# USB_PD_Source.net
KiCad netlist of a schematic drawn in Altium Designer
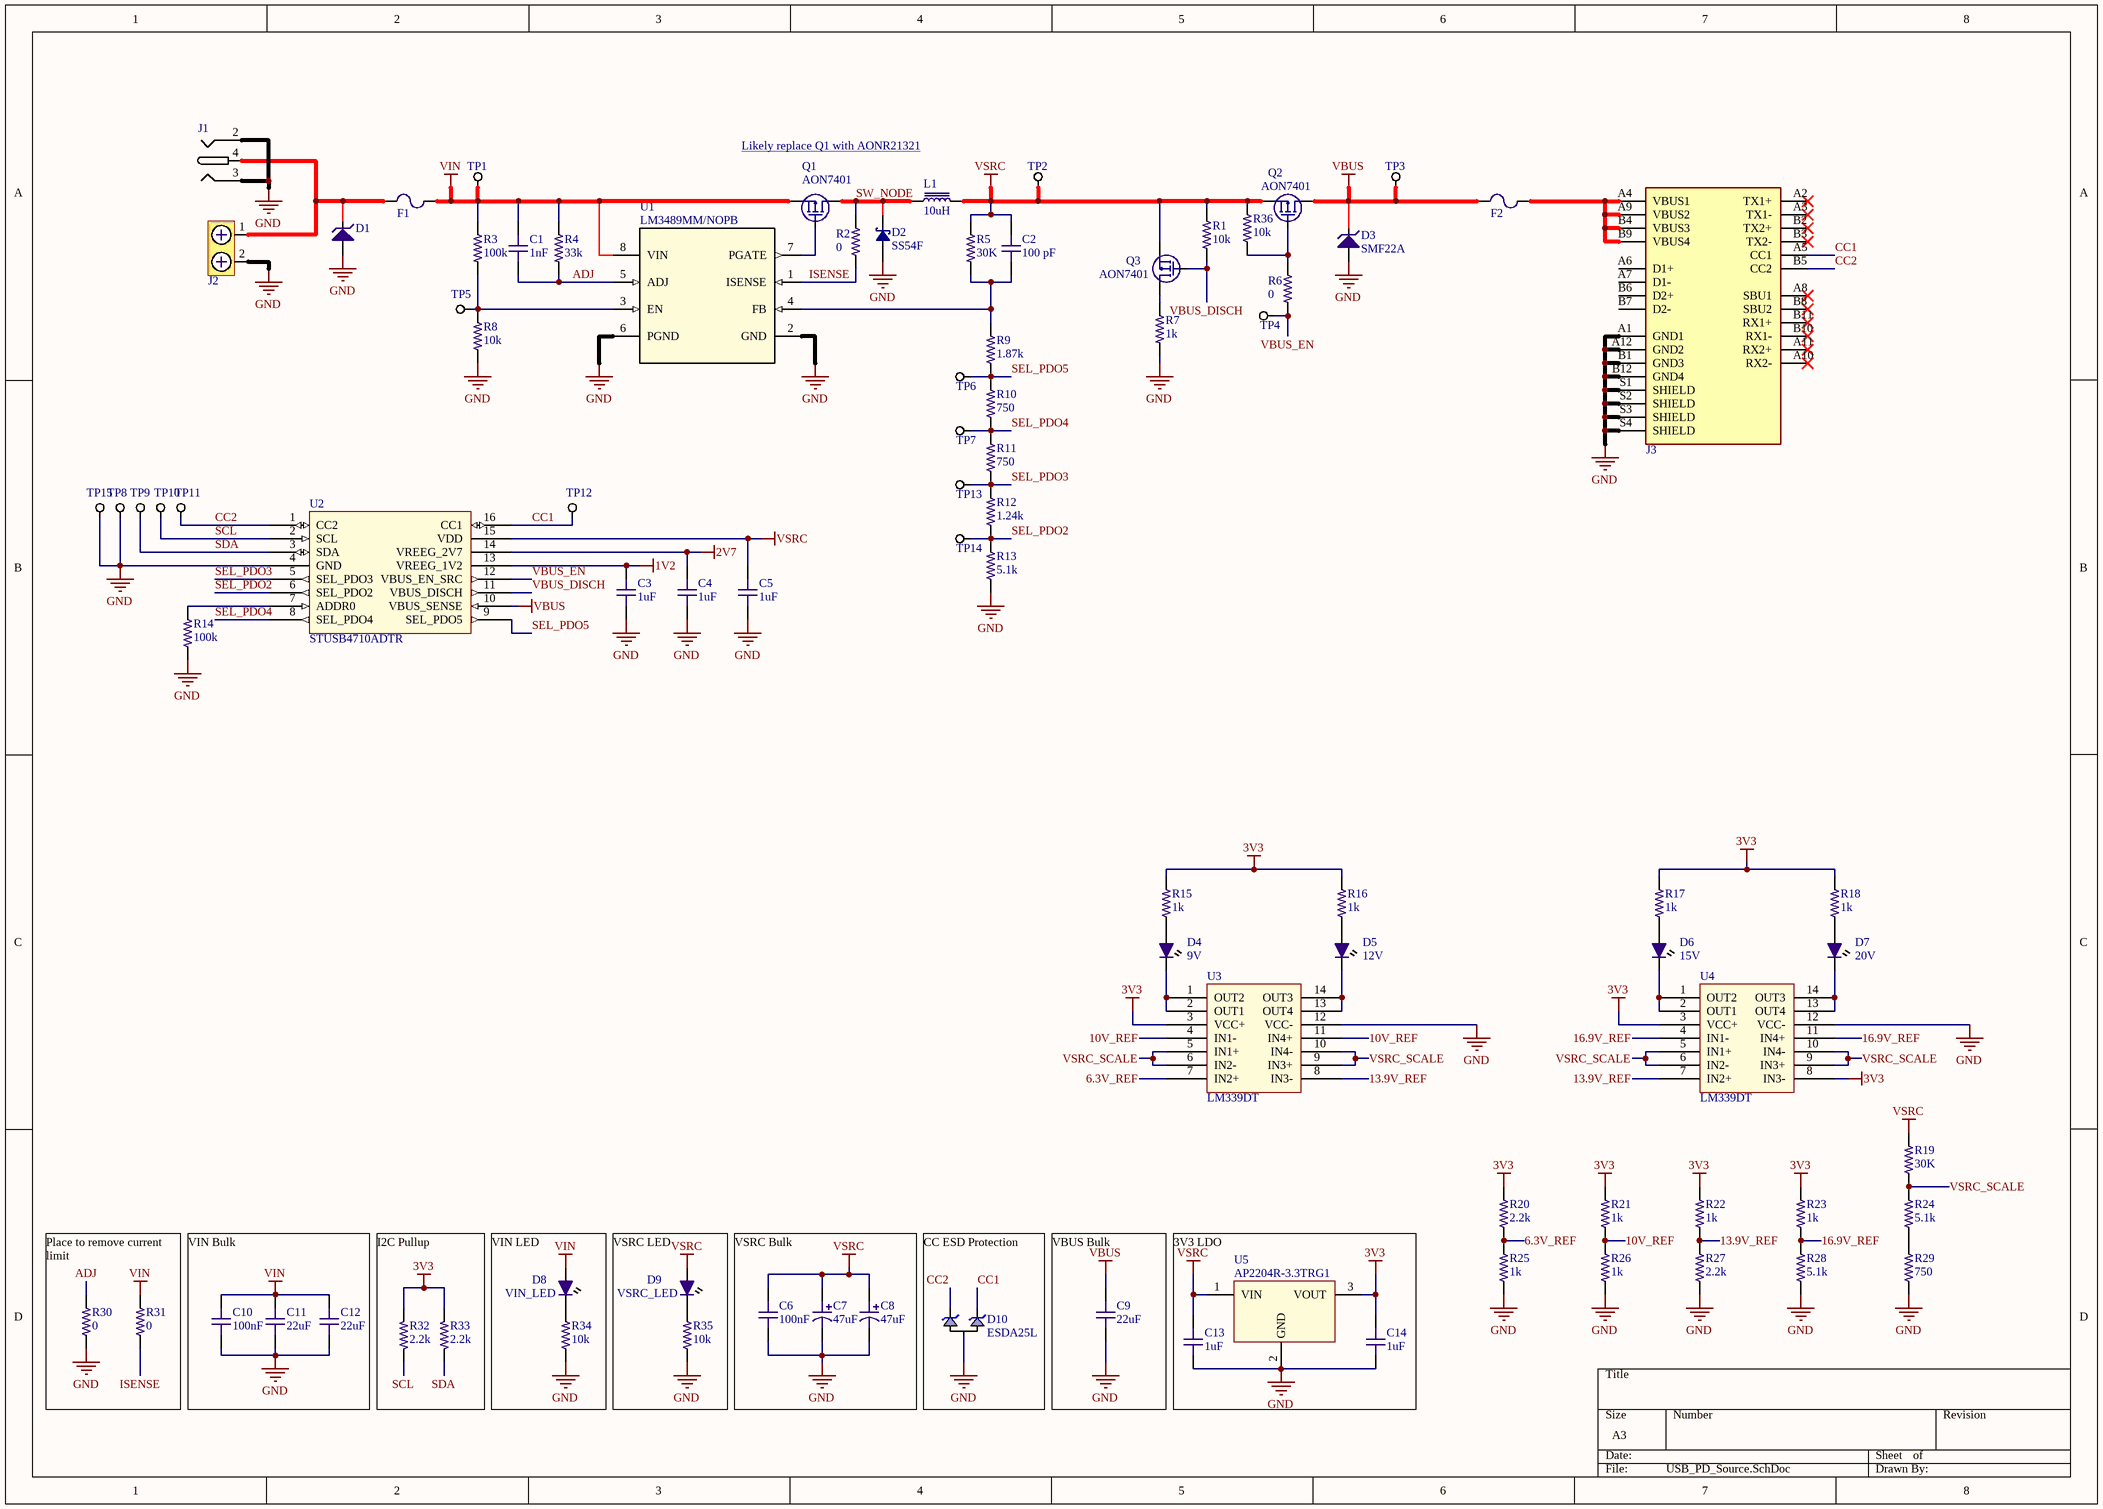
[diagram p0: USB_PD_Source.SchDoc]

(export (version "E")
  (design (tool "Eeschema 10.0.6"))
  (components
    (comp (ref "C1")
      (value "1nF")
      (footprint "C0603-IPC")
      (description "CAP CER 1000PF 100V X7R 0603")
      (fields (field (name "Comment") "C0603 1nF 100V X7R"))
      (libsource (lib "Capacitors") (part "C0603 1nF 100V X7R"))
    )
    (comp (ref "C2")
      (value "100 pF")
      (footprint "C0603-HIGH-DENSITY")
      (description "100pF ±10% 50V Ceramic Capacitor X7R 0603 (1608 Metric)")
      (fields (field (name "Comment") "C0603 100pF 50V X7R"))
      (libsource (lib "Capacitors") (part "C0603 100pF 50V X7R"))
    )
    (comp (ref "C3")
      (value "1uF")
      (footprint "C0603-IPC")
      (description "CAP CER 1UF 25V X7R 0603")
      (fields (field (name "Comment") "C0603 1uF 25V X7R"))
      (libsource (lib "Capacitors") (part "C0603 1uF 25V X7R"))
    )
    (comp (ref "C4")
      (value "1uF")
      (footprint "C0603-IPC")
      (description "CAP CER 1UF 25V X7R 0603")
      (fields (field (name "Comment") "C0603 1uF 25V X7R"))
      (libsource (lib "Capacitors") (part "C0603 1uF 25V X7R"))
    )
    (comp (ref "C5")
      (value "1uF")
      (footprint "C0603-IPC")
      (description "CAP CER 1UF 25V X7R 0603")
      (fields (field (name "Comment") "C0603 1uF 25V X7R"))
      (libsource (lib "Capacitors") (part "C0603 1uF 25V X7R"))
    )
    (comp (ref "C6")
      (value "100nF")
      (footprint "C0603-IPC")
      (description "CAP CER 0.1UF 50V X7R 0603")
      (fields (field (name "Comment") "C0603 100nF 50V X7R"))
      (libsource (lib "Capacitors") (part "C0603 100nF 50V X7R"))
    )
    (comp (ref "C7")
      (value "47uF")
      (footprint "C-SMD-Polarized-6.3x7.7mm")
      (description "47uF ±20% 50V SMD,6.3x7.7mm Aluminum Electrolytic Capacitors - SMD")
      (fields (field (name "Comment") "UUR1H470MCL6GS"))
      (libsource (lib "Capacitors") (part "C-SMD 47uF 50V Electrolytic"))
    )
    (comp (ref "C8")
      (value "47uF")
      (footprint "C-SMD-Polarized-6.3x7.7mm")
      (description "47uF ±20% 50V SMD,6.3x7.7mm Aluminum Electrolytic Capacitors - SMD")
      (fields (field (name "Comment") "UUR1H470MCL6GS"))
      (libsource (lib "Capacitors") (part "C-SMD 47uF 50V Electrolytic"))
    )
    (comp (ref "C9")
      (value "22uF")
      (footprint "C0603-IPC")
      (description "Chip Capacitor, 0603, 22uF, 25V, X5R")
      (fields (field (name "Comment") "C0603 22uF 25V X5R"))
      (libsource (lib "Capacitors") (part "C0603 22uF 10V X5R"))
    )
    (comp (ref "C10")
      (value "100nF")
      (footprint "C0603-IPC")
      (description "CAP CER 0.1UF 50V X7R 0603")
      (fields (field (name "Comment") "C0603 100nF 50V X7R"))
      (libsource (lib "Capacitors") (part "C0603 100nF 50V X7R"))
    )
    (comp (ref "C11")
      (value "22uF")
      (footprint "C0603-IPC")
      (description "Chip Capacitor, 0603, 22uF, 25V, X5R")
      (fields (field (name "Comment") "C0603 22uF 25V X5R"))
      (libsource (lib "Capacitors") (part "C0603 22uF 10V X5R"))
    )
    (comp (ref "C12")
      (value "22uF")
      (footprint "C0603-IPC")
      (description "Chip Capacitor, 0603, 22uF, 25V, X5R")
      (fields (field (name "Comment") "C0603 22uF 25V X5R"))
      (libsource (lib "Capacitors") (part "C0603 22uF 10V X5R"))
    )
    (comp (ref "C13")
      (value "1uF")
      (footprint "C0603-IPC")
      (description "CAP CER 1UF 25V X7R 0603")
      (fields (field (name "Comment") "C0603 1uF 25V X7R"))
      (libsource (lib "Capacitors") (part "C0603 1uF 25V X7R"))
    )
    (comp (ref "C14")
      (value "1uF")
      (footprint "C0603-IPC")
      (description "CAP CER 1UF 25V X7R 0603")
      (fields (field (name "Comment") "C0603 1uF 25V X7R"))
      (libsource (lib "Capacitors") (part "C0603 1uF 25V X7R"))
    )
    (comp (ref "D1")
      (value "GLZJ33C_R1_10001")
      (footprint "Mini-MELF Zener")
      (description "33V 500mW MINI-MELF Zener Diodes")
      (fields (field (name "MANUFACTURER") "PANJIT International"))
      (libsource (lib "Diodes") (part "GLZJ33C_R1_10001"))
    )
    (comp (ref "D2")
      (value "SS54F")
      (footprint "SMAF - SS54F")
      (description "40V 5A 550mV @ 5A SMAF Schottky Barrier Diodes (SBD) RoHS")
      (libsource (lib "Diodes") (part "SS54F"))
    )
    (comp (ref "D3")
      (value "SMF22A")
      (footprint "SOD-123F")
      (description "Unidirectional 22V 24.4V 35.5V 5.6A SOD-123F TVS RoHS")
      (fields (field (name "MANUFACTURER") "Littlefuse Inc."))
      (libsource (lib "Diodes") (part "SMF22A"))
    )
    (comp (ref "D4")
      (value "9V")
      (footprint "LED0603-IPC")
      (description "LED GREEN CLEAR 0603 SMD")
      (libsource (lib "Diodes") (part "LED 0603 Green"))
    )
    (comp (ref "D5")
      (value "12V")
      (footprint "LED0603-IPC")
      (description "LED GREEN CLEAR 0603 SMD")
      (libsource (lib "Diodes") (part "LED 0603 Green"))
    )
    (comp (ref "D6")
      (value "15V")
      (footprint "LED0603-IPC")
      (description "LED GREEN CLEAR 0603 SMD")
      (libsource (lib "Diodes") (part "LED 0603 Green"))
    )
    (comp (ref "D7")
      (value "20V")
      (footprint "LED0603-IPC")
      (description "LED GREEN CLEAR 0603 SMD")
      (libsource (lib "Diodes") (part "LED 0603 Green"))
    )
    (comp (ref "D8")
      (value "VIN_LED")
      (footprint "LED0603-IPC")
      (description "LED GREEN CLEAR 0603 SMD")
      (libsource (lib "Diodes") (part "LED 0603 Green"))
    )
    (comp (ref "D9")
      (value "VSRC_LED")
      (footprint "LED0603-IPC")
      (description "LED GREEN CLEAR 0603 SMD")
      (libsource (lib "Diodes") (part "LED 0603 Green"))
    )
    (comp (ref "D10")
      (value "ESDA25L")
      (footprint "SOT23-3L")
      (description "Dual Transil Array For ESD Protection in SOT23-3 Vbr = 25V")
      (fields (field (name "MANUFACTURER") "STMicroelectronics"))
      (libsource (lib "Diodes") (part "ESDA25L"))
    )
    (comp (ref "F1")
      (value "JFC1206-2150FS")
      (footprint "F1206-12A")
      (description "Chip Fuse Fast Blow 15A 2.9mΩ 66mV 150A 23.89 1206 Surface Mount Fuses")
      (libsource (lib "Virtual Parts") (part "F1206 15A"))
    )
    (comp (ref "F2")
      (value "JFC1206-2150FS")
      (footprint "F1206-12A")
      (description "Chip Fuse Fast Blow 15A 2.9mΩ 66mV 150A 23.89 1206 Surface Mount Fuses")
      (libsource (lib "Virtual Parts") (part "F1206 15A"))
    )
    (comp (ref "J1")
      (value "DC-042C-2.5")
      (footprint "DC-042C-2.5 THT BARREL JACK")
      (description "DC Power Receptacle Jack 8A 2.5mm DIP AC/DC Power Plugs & Receptacles")
      (libsource (lib "Connectors") (part "DC Barrel Jack 2.5 x 5.5mm THT"))
    )
    (comp (ref "J2")
      (value "Phoenix Contact 1935161")
      (footprint "Phoenix_1935161")
      (description "Terminal Block, 2 Position, 5mm pitch, 18A, 300V, 12-26 AWG")
      (fields
        (field (name "MANUFACTURER") "Phoenix Contact")
        (field (name "MANUFACTURER PART NUMBER") "1935161")
      )
      (libsource (lib "Connectors") (part "Term Block 2pos"))
    )
    (comp (ref "J3")
      (value "USB C")
      (footprint "Molex USB-C")
      (fields
        (field (name "MF") "Molex")
        (field (name "DIGI-KEY_PART_NUMBER") "WM12856CT-ND")
        (field (name "MP") "1054500101")
      )
      (libsource (lib "Connectors") (part "USB C"))
    )
    (comp (ref "L1")
      (value "TMPA1206SP-100MN-D")
      (footprint "TMPA1206SP-100MN-D")
      (description "10uH ±20% 10.5A 15.5mΩ SMD,13.5x12.6x5.7mm Power Inductors RoHS")
      (fields (field (name "INDUCTANCE") "10uH"))
      (libsource (lib "Inductors") (part "TMPA1206SP-100MN-D"))
    )
    (comp (ref "Q1")
      (value "AON7401")
      (footprint "DFN3x3A_8L_EP1_P")
      (description "P-Channel 30V 12A (Ta), 35A (Tc) 3.1W (Ta), 29W (Tc) Surface Mount 8-DFN (3x3)")
      (libsource (lib "Transistors") (part "AON7401"))
    )
    (comp (ref "Q2")
      (value "AON7401")
      (footprint "DFN3x3A_8L_EP1_P")
      (description "P-Channel 30V 12A (Ta), 35A (Tc) 3.1W (Ta), 29W (Tc) Surface Mount 8-DFN (3x3)")
      (libsource (lib "Transistors") (part "AON7401"))
    )
    (comp (ref "Q3")
      (value "AON7401")
      (footprint "DFN3x3A_8L_EP1_P")
      (description "P-Channel 30V 12A (Ta), 35A (Tc) 3.1W (Ta), 29W (Tc) Surface Mount 8-DFN (3x3)")
      (libsource (lib "Transistors") (part "AON7401"))
    )
    (comp (ref "R1")
      (value "10k")
      (footprint "R0603-IPC-10K")
      (description "RES SMD 10K OHM 1% 1/10W 0603")
      (fields (field (name "Comment") "R0603 10K 1%"))
      (libsource (lib "Resistors") (part "R0603 10K 1%"))
    )
    (comp (ref "R2")
      (value "0")
      (footprint "R0603-IPC")
      (description "RES SMD 0 OHM JUMPER 1/10W 0603")
      (fields (field (name "Comment") "R0603 0"))
      (libsource (lib "Resistors") (part "R0603 0"))
    )
    (comp (ref "R3")
      (value "100k")
      (footprint "R0603-IPC")
      (description "RES SMD 100K OHM 1% 1/10W 0603")
      (fields (field (name "Comment") "R0603 100K 1%"))
      (libsource (lib "Resistors") (part "R0603 100K 1%"))
    )
    (comp (ref "R4")
      (value "33k")
      (footprint "R0603-IPC")
      (description "RES 33K OHM 1% 1/10W 0603")
      (fields (field (name "Comment") "R0603 33k 1%"))
      (libsource (lib "Resistors") (part "R0603 33k 1%"))
    )
    (comp (ref "R5")
      (value "30K")
      (footprint "R0603-IPC")
      (description "RES SMD 30K OHM 1% 1/10W 0603")
      (fields (field (name "Comment") "R0603 30k 1%"))
      (libsource (lib "Resistors") (part "R0603 30k 1%"))
    )
    (comp (ref "R6")
      (value "0")
      (footprint "R0603-IPC")
      (description "RES SMD 0 OHM JUMPER 1/10W 0603")
      (fields (field (name "Comment") "R0603 0"))
      (libsource (lib "Resistors") (part "R0603 0"))
    )
    (comp (ref "R7")
      (value "1k")
      (footprint "R0603-IPC-1K")
      (description "RES SMD 1K OHM 1% 1/10W 0603")
      (fields (field (name "TOLERANCE") "±1%") (field (name "Comment") "R0603 1K 1%"))
      (libsource (lib "Resistors") (part "R0603 1K 1%"))
    )
    (comp (ref "R8")
      (value "10k")
      (footprint "R0603-IPC-10K")
      (description "RES SMD 10K OHM 1% 1/10W 0603")
      (fields (field (name "Comment") "R0603 10K 1%"))
      (libsource (lib "Resistors") (part "R0603 10K 1%"))
    )
    (comp (ref "R9")
      (value "1.87k")
      (footprint "R0603-IPC-1.87k")
      (description "Chip Resistor, 0603, 1.87k ohms, 1%, 1/10 W")
      (fields (field (name "Comment") "RES 1.87K SMD"))
      (libsource (lib "Resistors") (part "R0603 1.87k 1%"))
    )
    (comp (ref "R10")
      (value "750")
      (footprint "R0603-IPC-750R")
      (description "Chip Resistor, 0603, 750 ohms, 0.1W")
      (fields (field (name "Comment") "R0603 750 1%"))
      (libsource (lib "Resistors") (part "R0603 750 1%"))
    )
    (comp (ref "R11")
      (value "750")
      (footprint "R0603-IPC-750R")
      (description "Chip Resistor, 0603, 750 ohms, 0.1W")
      (fields (field (name "Comment") "R0603 750 1%"))
      (libsource (lib "Resistors") (part "R0603 750 1%"))
    )
    (comp (ref "R12")
      (value "1.24k")
      (footprint "R0603-IPC")
      (description "Chip Resistor, 0603, 1.24k ohms, 0.5%, 1/10 W")
      (fields (field (name "Comment") "ERA3AED1241V"))
      (libsource (lib "Resistors") (part "R0603 1.24k 0.5%"))
    )
    (comp (ref "R13")
      (value "5.1k")
      (footprint "R0603-IPC-5.1K")
      (description "RES SMD 5.1K OHM 1% 1/10W 0603")
      (fields (field (name "Comment") "R0603 5.1K 1%"))
      (libsource (lib "Resistors") (part "R0603 5.1K 1%"))
    )
    (comp (ref "R14")
      (value "100k")
      (footprint "R0603-IPC")
      (description "RES SMD 100K OHM 1% 1/10W 0603")
      (fields (field (name "Comment") "R0603 100K 1%"))
      (libsource (lib "Resistors") (part "R0603 100K 1%"))
    )
    (comp (ref "R15")
      (value "1k")
      (footprint "R0603-IPC-1K")
      (description "RES SMD 1K OHM 1% 1/10W 0603")
      (fields (field (name "TOLERANCE") "±1%") (field (name "Comment") "R0603 1K 1%"))
      (libsource (lib "Resistors") (part "R0603 1K 1%"))
    )
    (comp (ref "R16")
      (value "1k")
      (footprint "R0603-IPC-1K")
      (description "RES SMD 1K OHM 1% 1/10W 0603")
      (fields (field (name "TOLERANCE") "±1%") (field (name "Comment") "R0603 1K 1%"))
      (libsource (lib "Resistors") (part "R0603 1K 1%"))
    )
    (comp (ref "R17")
      (value "1k")
      (footprint "R0603-IPC-1K")
      (description "RES SMD 1K OHM 1% 1/10W 0603")
      (fields (field (name "TOLERANCE") "±1%") (field (name "Comment") "R0603 1K 1%"))
      (libsource (lib "Resistors") (part "R0603 1K 1%"))
    )
    (comp (ref "R18")
      (value "1k")
      (footprint "R0603-IPC-1K")
      (description "RES SMD 1K OHM 1% 1/10W 0603")
      (fields (field (name "TOLERANCE") "±1%") (field (name "Comment") "R0603 1K 1%"))
      (libsource (lib "Resistors") (part "R0603 1K 1%"))
    )
    (comp (ref "R19")
      (value "30K")
      (footprint "R0603-IPC")
      (description "RES SMD 30K OHM 1% 1/10W 0603")
      (fields (field (name "Comment") "R0603 30k 1%"))
      (libsource (lib "Resistors") (part "R0603 30k 1%"))
    )
    (comp (ref "R20")
      (value "2.2k")
      (footprint "R0603-IPC")
      (description "RES SMD 2.2K OHM 1% 1/10W 0603")
      (fields (field (name "Comment") "R0603 2.2K 1%"))
      (libsource (lib "Resistors") (part "R0603 2.2K 1%"))
    )
    (comp (ref "R21")
      (value "1k")
      (footprint "R0603-IPC-1K")
      (description "RES SMD 1K OHM 1% 1/10W 0603")
      (fields (field (name "TOLERANCE") "±1%") (field (name "Comment") "R0603 1K 1%"))
      (libsource (lib "Resistors") (part "R0603 1K 1%"))
    )
    (comp (ref "R22")
      (value "1k")
      (footprint "R0603-IPC-1K")
      (description "RES SMD 1K OHM 1% 1/10W 0603")
      (fields (field (name "TOLERANCE") "±1%") (field (name "Comment") "R0603 1K 1%"))
      (libsource (lib "Resistors") (part "R0603 1K 1%"))
    )
    (comp (ref "R23")
      (value "1k")
      (footprint "R0603-IPC-1K")
      (description "RES SMD 1K OHM 1% 1/10W 0603")
      (fields (field (name "TOLERANCE") "±1%") (field (name "Comment") "R0603 1K 1%"))
      (libsource (lib "Resistors") (part "R0603 1K 1%"))
    )
    (comp (ref "R24")
      (value "5.1k")
      (footprint "R0603-IPC-5.1K")
      (description "RES SMD 5.1K OHM 1% 1/10W 0603")
      (fields (field (name "Comment") "R0603 5.1K 1%"))
      (libsource (lib "Resistors") (part "R0603 5.1K 1%"))
    )
    (comp (ref "R25")
      (value "1k")
      (footprint "R0603-IPC-1K")
      (description "RES SMD 1K OHM 1% 1/10W 0603")
      (fields (field (name "TOLERANCE") "±1%") (field (name "Comment") "R0603 1K 1%"))
      (libsource (lib "Resistors") (part "R0603 1K 1%"))
    )
    (comp (ref "R26")
      (value "1k")
      (footprint "R0603-IPC-1K")
      (description "RES SMD 1K OHM 1% 1/10W 0603")
      (fields (field (name "TOLERANCE") "±1%") (field (name "Comment") "R0603 1K 1%"))
      (libsource (lib "Resistors") (part "R0603 1K 1%"))
    )
    (comp (ref "R27")
      (value "2.2k")
      (footprint "R0603-IPC")
      (description "RES SMD 2.2K OHM 1% 1/10W 0603")
      (fields (field (name "Comment") "R0603 2.2K 1%"))
      (libsource (lib "Resistors") (part "R0603 2.2K 1%"))
    )
    (comp (ref "R28")
      (value "5.1k")
      (footprint "R0603-IPC-5.1K")
      (description "RES SMD 5.1K OHM 1% 1/10W 0603")
      (fields (field (name "Comment") "R0603 5.1K 1%"))
      (libsource (lib "Resistors") (part "R0603 5.1K 1%"))
    )
    (comp (ref "R29")
      (value "750")
      (footprint "R0603-IPC-750R")
      (description "Chip Resistor, 0603, 750 ohms, 0.1W")
      (fields (field (name "Comment") "R0603 750 1%"))
      (libsource (lib "Resistors") (part "R0603 750 1%"))
    )
    (comp (ref "R30")
      (value "0")
      (footprint "R0603-IPC")
      (description "RES SMD 0 OHM JUMPER 1/10W 0603")
      (fields (field (name "Comment") "R0603 0"))
      (libsource (lib "Resistors") (part "R0603 0"))
    )
    (comp (ref "R31")
      (value "0")
      (footprint "R0603-IPC")
      (description "RES SMD 0 OHM JUMPER 1/10W 0603")
      (fields (field (name "Comment") "R0603 0"))
      (libsource (lib "Resistors") (part "R0603 0"))
    )
    (comp (ref "R32")
      (value "2.2k")
      (footprint "R0603-IPC")
      (description "RES SMD 2.2K OHM 1% 1/10W 0603")
      (fields (field (name "Comment") "R0603 2.2K 1%"))
      (libsource (lib "Resistors") (part "R0603 2.2K 1%"))
    )
    (comp (ref "R33")
      (value "2.2k")
      (footprint "R0603-IPC")
      (description "RES SMD 2.2K OHM 1% 1/10W 0603")
      (fields (field (name "Comment") "R0603 2.2K 1%"))
      (libsource (lib "Resistors") (part "R0603 2.2K 1%"))
    )
    (comp (ref "R34")
      (value "10k")
      (footprint "R0603-HIGH-DENSITY")
      (description "RES SMD 10K OHM 1% 1/10W 0603")
      (fields (field (name "Comment") "R0603 10K 1%"))
      (libsource (lib "Resistors") (part "R0603 10K 1%"))
    )
    (comp (ref "R35")
      (value "10k")
      (footprint "R0603-IPC-10K")
      (description "RES SMD 10K OHM 1% 1/10W 0603")
      (fields (field (name "Comment") "R0603 10K 1%"))
      (libsource (lib "Resistors") (part "R0603 10K 1%"))
    )
    (comp (ref "R36")
      (value "10k")
      (footprint "R0603-IPC-10K")
      (description "RES SMD 10K OHM 1% 1/10W 0603")
      (fields (field (name "Comment") "R0603 10K 1%"))
      (libsource (lib "Resistors") (part "R0603 10K 1%"))
    )
    (comp (ref "TP1")
      (value "VIN")
      (footprint "Testpoint_TH")
      (description "Through-hole testpoint hook")
      (libsource (lib "Virtual Parts") (part "Testpoint_TH"))
    )
    (comp (ref "TP2")
      (value "VSRC")
      (footprint "Testpoint_TH")
      (description "Through-hole testpoint hook")
      (libsource (lib "Virtual Parts") (part "Testpoint_TH"))
    )
    (comp (ref "TP3")
      (value "VBUS")
      (footprint "Testpoint_TH")
      (description "Through-hole testpoint hook")
      (libsource (lib "Virtual Parts") (part "Testpoint_TH"))
    )
    (comp (ref "TP4")
      (value "VBUS_EN")
      (footprint "Testpoint_TH")
      (description "Through-hole testpoint hook")
      (libsource (lib "Virtual Parts") (part "Testpoint_TH"))
    )
    (comp (ref "TP5")
      (value "BUCK_EN")
      (footprint "Testpoint_TH")
      (description "Through-hole testpoint hook")
      (libsource (lib "Virtual Parts") (part "Testpoint_TH"))
    )
    (comp (ref "TP6")
      (value "PDO2_N")
      (footprint "Testpoint_TH")
      (description "Through-hole testpoint hook")
      (libsource (lib "Virtual Parts") (part "Testpoint_TH"))
    )
    (comp (ref "TP7")
      (value "PDO3_N")
      (footprint "Testpoint_TH")
      (description "Through-hole testpoint hook")
      (libsource (lib "Virtual Parts") (part "Testpoint_TH"))
    )
    (comp (ref "TP8")
      (value "GNDD")
      (footprint "Testpoint_TH")
      (description "Through-hole testpoint hook")
      (libsource (lib "Virtual Parts") (part "Testpoint_TH"))
    )
    (comp (ref "TP9")
      (value "SDA")
      (footprint "Testpoint_TH")
      (description "Through-hole testpoint hook")
      (libsource (lib "Virtual Parts") (part "Testpoint_TH"))
    )
    (comp (ref "TP10")
      (value "SCL")
      (footprint "Testpoint_TH")
      (description "Through-hole testpoint hook")
      (libsource (lib "Virtual Parts") (part "Testpoint_TH"))
    )
    (comp (ref "TP11")
      (value "CC2")
      (footprint "Testpoint_TH")
      (description "Through-hole testpoint hook")
      (libsource (lib "Virtual Parts") (part "Testpoint_TH"))
    )
    (comp (ref "TP12")
      (value "CC1")
      (footprint "Testpoint_TH")
      (description "Through-hole testpoint hook")
      (libsource (lib "Virtual Parts") (part "Testpoint_TH"))
    )
    (comp (ref "TP13")
      (value "PDO4_N")
      (footprint "Testpoint_TH")
      (description "Through-hole testpoint hook")
      (libsource (lib "Virtual Parts") (part "Testpoint_TH"))
    )
    (comp (ref "TP14")
      (value "PDO5_N")
      (footprint "Testpoint_TH")
      (description "Through-hole testpoint hook")
      (libsource (lib "Virtual Parts") (part "Testpoint_TH"))
    )
    (comp (ref "TP15")
      (value "Testpoint_TH")
      (footprint "Testpoint_TH")
      (description "Through-hole testpoint hook")
      (libsource (lib "Virtual Parts") (part "Testpoint_TH"))
    )
    (comp (ref "U1")
      (value "LM3489MM/NOPB")
      (footprint "DGK (S-PDSO-G8) - LM3489")
      (description "Buck Regulator Positive Output Step-Down DC-DC Controller IC 8-VSSOP")
      (libsource (lib "Integrated Circuits") (part "LM3489MM"))
    )
    (comp (ref "U2")
      (value "STUSB4710ADTR")
      (footprint "SO-16")
      (description "Standalone USB PD controller  with Source in 16-SO package")
      (fields
        (field (name "PART NUMBER") "Standalone USB PD controller  with SINK auto-run mode in QFN24 4x4mm")
        (field (name "MANUFACTURER") "STMicroelectronics")
      )
      (libsource (lib "Integrated Circuits") (part "STUSB4710ADTR"))
    )
    (comp (ref "U3")
      (value "LM339DT")
      (footprint "SO-14 (LM339DT)")
      (description "Quad Comparator General Purpose CMOS, DTL, ECL, MOS, Open-Collector, TTL 14-SO, 2-32V")
      (libsource (lib "Integrated Circuits") (part "LM339DT"))
    )
    (comp (ref "U4")
      (value "LM339DT")
      (footprint "SO-14 (LM339DT)")
      (description "Quad Comparator General Purpose CMOS, DTL, ECL, MOS, Open-Collector, TTL 14-SO, 2-32V")
      (libsource (lib "Integrated Circuits") (part "LM339DT"))
    )
    (comp (ref "U5")
      (value "AP2204R-3.3TRG1")
      (footprint "SOT-89")
      (description "Fixed 24V 3.3V 150mA SOT-89(SOT-89-3) Low Dropout Regulators(LDO)")
      (libsource (lib "Integrated Circuits") (part "AP2204R-3.3TRG1"))
    )
  )
  (nets
    (net (code "1") (name "/6.3V_REF") (class "Default")
      (node (ref "R20") (pin "1") (pintype "passive"))
      (node (ref "R25") (pin "1") (pintype "passive"))
      (node (ref "U3") (pin "7") (pinfunction "IN2+_7") (pintype "passive"))
    )
    (net (code "2") (name "/10V_REF") (class "Default")
      (node (ref "R21") (pin "2") (pintype "passive"))
      (node (ref "R26") (pin "1") (pintype "passive"))
      (node (ref "U3") (pin "11") (pinfunction "IN4+_11") (pintype "passive"))
      (node (ref "U3") (pin "4") (pinfunction "IN1-_4") (pintype "passive"))
    )
    (net (code "3") (name "/13.9V_REF") (class "Default")
      (node (ref "R22") (pin "2") (pintype "passive"))
      (node (ref "R27") (pin "2") (pintype "passive"))
      (node (ref "U3") (pin "8") (pinfunction "IN3-_8") (pintype "passive"))
      (node (ref "U4") (pin "7") (pinfunction "IN2+_7") (pintype "passive"))
    )
    (net (code "4") (name "/16.9V_REF") (class "Default")
      (node (ref "R23") (pin "2") (pintype "passive"))
      (node (ref "R28") (pin "2") (pintype "passive"))
      (node (ref "U4") (pin "11") (pinfunction "IN4+_11") (pintype "passive"))
      (node (ref "U4") (pin "4") (pinfunction "IN1-_4") (pintype "passive"))
    )
    (net (code "5") (name "/ADJ") (class "Default")
      (node (ref "C1") (pin "1") (pintype "passive"))
      (node (ref "R30") (pin "2") (pintype "passive"))
      (node (ref "R4") (pin "1") (pintype "passive"))
      (node (ref "U1") (pin "5") (pinfunction "ADJ_5") (pintype "input"))
    )
    (net (code "6") (name "/CC1") (class "Default")
      (node (ref "D10") (pin "1") (pinfunction "K1_1") (pintype "passive"))
      (node (ref "J3") (pin "A5") (pinfunction "CC1_A5") (pintype "passive"))
      (node (ref "TP12") (pin "1") (pinfunction "1_1") (pintype "passive"))
      (node (ref "U2") (pin "16") (pinfunction "CC1_16") (pintype "bidirectional"))
    )
    (net (code "7") (name "/CC2") (class "Default")
      (node (ref "D10") (pin "2") (pinfunction "K2_2") (pintype "power_in"))
      (node (ref "J3") (pin "B5") (pinfunction "CC2_B5") (pintype "passive"))
      (node (ref "TP11") (pin "1") (pinfunction "1_1") (pintype "passive"))
      (node (ref "U2") (pin "1") (pinfunction "CC2_1") (pintype "bidirectional"))
    )
    (net (code "8") (name "/ISENSE") (class "Default")
      (node (ref "R2") (pin "1") (pintype "passive"))
      (node (ref "R31") (pin "1") (pintype "passive"))
      (node (ref "U1") (pin "1") (pinfunction "ISENSE_1") (pintype "input"))
    )
    (net (code "9") (name "/SCL") (class "Default")
      (node (ref "R32") (pin "2") (pintype "passive"))
      (node (ref "TP10") (pin "1") (pinfunction "1_1") (pintype "passive"))
      (node (ref "U2") (pin "2") (pinfunction "SCL_2") (pintype "input"))
    )
    (net (code "10") (name "/SDA") (class "Default")
      (node (ref "R33") (pin "2") (pintype "passive"))
      (node (ref "TP9") (pin "1") (pinfunction "1_1") (pintype "passive"))
      (node (ref "U2") (pin "3") (pinfunction "SDA_3") (pintype "bidirectional"))
    )
    (net (code "11") (name "/SEL_PDO2") (class "Default")
      (node (ref "R12") (pin "2") (pintype "passive"))
      (node (ref "R13") (pin "1") (pintype "passive"))
      (node (ref "TP14") (pin "1") (pinfunction "1_1") (pintype "passive"))
      (node (ref "U2") (pin "6") (pinfunction "SEL_PDO2_6") (pintype "output"))
    )
    (net (code "12") (name "/SEL_PDO3") (class "Default")
      (node (ref "R11") (pin "2") (pintype "passive"))
      (node (ref "R12") (pin "1") (pintype "passive"))
      (node (ref "TP13") (pin "1") (pinfunction "1_1") (pintype "passive"))
      (node (ref "U2") (pin "5") (pinfunction "SEL_PDO3_5") (pintype "output"))
    )
    (net (code "13") (name "/SEL_PDO4") (class "Default")
      (node (ref "R10") (pin "2") (pintype "passive"))
      (node (ref "R11") (pin "1") (pintype "passive"))
      (node (ref "TP7") (pin "1") (pinfunction "1_1") (pintype "passive"))
      (node (ref "U2") (pin "8") (pinfunction "SEL_PDO4_8") (pintype "output"))
    )
    (net (code "14") (name "/SEL_PDO5") (class "Default")
      (node (ref "R10") (pin "1") (pintype "passive"))
      (node (ref "R9") (pin "2") (pintype "passive"))
      (node (ref "TP6") (pin "1") (pinfunction "1_1") (pintype "passive"))
      (node (ref "U2") (pin "9") (pinfunction "SEL_PDO5_9") (pintype "output"))
    )
    (net (code "15") (name "/SW_NODE") (class "Default")
      (node (ref "D2") (pin "K") (pinfunction "K_K") (pintype "passive"))
      (node (ref "L1") (pin "1") (pintype "passive"))
      (node (ref "Q1") (pin "D") (pinfunction "D_D") (pintype "passive"))
      (node (ref "R2") (pin "2") (pintype "passive"))
    )
    (net (code "16") (name "/VBUS_DISCH") (class "Default")
      (node (ref "Q3") (pin "G") (pinfunction "G_G") (pintype "passive"))
      (node (ref "R1") (pin "1") (pintype "passive"))
      (node (ref "U2") (pin "11") (pinfunction "VBUS_DISCH_11") (pintype "output"))
    )
    (net (code "17") (name "/VBUS_EN") (class "Default")
      (node (ref "R6") (pin "1") (pintype "passive"))
      (node (ref "TP4") (pin "1") (pinfunction "1_1") (pintype "passive"))
      (node (ref "U2") (pin "12") (pinfunction "VBUS_EN_SRC_12") (pintype "output"))
    )
    (net (code "18") (name "/VSRC_SCALE") (class "Default")
      (node (ref "R19") (pin "2") (pintype "passive"))
      (node (ref "R24") (pin "2") (pintype "passive"))
      (node (ref "U3") (pin "10") (pinfunction "IN4-_10") (pintype "passive"))
      (node (ref "U3") (pin "5") (pinfunction "IN1+_5") (pintype "passive"))
      (node (ref "U3") (pin "6") (pinfunction "IN2-_6") (pintype "passive"))
      (node (ref "U3") (pin "9") (pinfunction "IN3+_9") (pintype "passive"))
      (node (ref "U4") (pin "10") (pinfunction "IN4-_10") (pintype "passive"))
      (node (ref "U4") (pin "5") (pinfunction "IN1+_5") (pintype "passive"))
      (node (ref "U4") (pin "6") (pinfunction "IN2-_6") (pintype "passive"))
      (node (ref "U4") (pin "9") (pinfunction "IN3+_9") (pintype "passive"))
    )
    (net (code "19") (name "1V2") (class "Default")
      (node (ref "C3") (pin "2") (pintype "passive"))
      (node (ref "U2") (pin "13") (pinfunction "VREEG_1V2_13") (pintype "power_in"))
    )
    (net (code "20") (name "2V7") (class "Default")
      (node (ref "C4") (pin "2") (pintype "passive"))
      (node (ref "U2") (pin "14") (pinfunction "VREEG_2V7_14") (pintype "power_in"))
    )
    (net (code "21") (name "3V3") (class "Default")
      (node (ref "C14") (pin "1") (pintype "passive"))
      (node (ref "R15") (pin "1") (pintype "passive"))
      (node (ref "R16") (pin "1") (pintype "passive"))
      (node (ref "R17") (pin "1") (pintype "passive"))
      (node (ref "R18") (pin "1") (pintype "passive"))
      (node (ref "R20") (pin "2") (pintype "passive"))
      (node (ref "R21") (pin "1") (pintype "passive"))
      (node (ref "R22") (pin "1") (pintype "passive"))
      (node (ref "R23") (pin "1") (pintype "passive"))
      (node (ref "R32") (pin "1") (pintype "passive"))
      (node (ref "R33") (pin "1") (pintype "passive"))
      (node (ref "U3") (pin "3") (pinfunction "VCC+_3") (pintype "passive"))
      (node (ref "U4") (pin "3") (pinfunction "VCC+_3") (pintype "passive"))
      (node (ref "U4") (pin "8") (pinfunction "IN3-_8") (pintype "passive"))
      (node (ref "U5") (pin "3") (pinfunction "VOUT_3") (pintype "passive"))
    )
    (net (code "22") (name "GND") (class "Default")
      (node (ref "C10") (pin "1") (pintype "passive"))
      (node (ref "C11") (pin "1") (pintype "passive"))
      (node (ref "C12") (pin "1") (pintype "passive"))
      (node (ref "C13") (pin "2") (pintype "passive"))
      (node (ref "C14") (pin "2") (pintype "passive"))
      (node (ref "C3") (pin "1") (pintype "passive"))
      (node (ref "C4") (pin "1") (pintype "passive"))
      (node (ref "C5") (pin "2") (pintype "passive"))
      (node (ref "C6") (pin "1") (pintype "passive"))
      (node (ref "C7") (pin "2") (pintype "passive"))
      (node (ref "C8") (pin "2") (pintype "passive"))
      (node (ref "C9") (pin "1") (pintype "passive"))
      (node (ref "D1") (pin "2") (pinfunction "A_2") (pintype "passive"))
      (node (ref "D10") (pin "3") (pinfunction "A_3") (pintype "passive"))
      (node (ref "D2") (pin "A") (pinfunction "A_A") (pintype "passive"))
      (node (ref "D3") (pin "A") (pinfunction "A_A") (pintype "passive"))
      (node (ref "J1") (pin "2") (pinfunction "2_2") (pintype "passive"))
      (node (ref "J1") (pin "3") (pinfunction "3_3") (pintype "passive"))
      (node (ref "J2") (pin "2") (pintype "passive"))
      (node (ref "J3") (pin "A1") (pinfunction "GND1_A1") (pintype "passive"))
      (node (ref "J3") (pin "A12") (pinfunction "GND2_A12") (pintype "passive"))
      (node (ref "J3") (pin "B1") (pinfunction "GND3_B1") (pintype "passive"))
      (node (ref "J3") (pin "B12") (pinfunction "GND4_B12") (pintype "passive"))
      (node (ref "J3") (pin "S1") (pinfunction "SHIELD_S1") (pintype "passive"))
      (node (ref "J3") (pin "S2") (pinfunction "SHIELD_S2") (pintype "passive"))
      (node (ref "J3") (pin "S3") (pinfunction "SHIELD_S3") (pintype "passive"))
      (node (ref "J3") (pin "S4") (pinfunction "SHIELD_S4") (pintype "passive"))
      (node (ref "R13") (pin "2") (pintype "passive"))
      (node (ref "R14") (pin "1") (pintype "passive"))
      (node (ref "R25") (pin "2") (pintype "passive"))
      (node (ref "R26") (pin "2") (pintype "passive"))
      (node (ref "R27") (pin "1") (pintype "passive"))
      (node (ref "R28") (pin "1") (pintype "passive"))
      (node (ref "R29") (pin "1") (pintype "passive"))
      (node (ref "R30") (pin "1") (pintype "passive"))
      (node (ref "R34") (pin "1") (pintype "passive"))
      (node (ref "R35") (pin "1") (pintype "passive"))
      (node (ref "R7") (pin "2") (pintype "passive"))
      (node (ref "R8") (pin "1") (pintype "passive"))
      (node (ref "TP15") (pin "1") (pinfunction "1_1") (pintype "passive"))
      (node (ref "TP8") (pin "1") (pinfunction "1_1") (pintype "passive"))
      (node (ref "U1") (pin "2") (pinfunction "GND_2") (pintype "power_in"))
      (node (ref "U1") (pin "6") (pinfunction "PGND_6") (pintype "power_in"))
      (node (ref "U2") (pin "4") (pinfunction "GND_4") (pintype "power_in"))
      (node (ref "U3") (pin "12") (pinfunction "VCC-_12") (pintype "passive"))
      (node (ref "U4") (pin "12") (pinfunction "VCC-_12") (pintype "passive"))
      (node (ref "U5") (pin "2") (pinfunction "GND_2") (pintype "passive"))
    )
    (net (code "23") (name "Net-(D1-K)") (class "Default")
      (node (ref "D1") (pin "1") (pinfunction "K_1") (pintype "passive"))
      (node (ref "F1") (pin "1") (pintype "passive"))
      (node (ref "J1") (pin "4") (pinfunction "4_4") (pintype "passive"))
      (node (ref "J2") (pin "1") (pintype "passive"))
    )
    (net (code "24") (name "Net-(D4-PadA)") (class "Default")
      (node (ref "D4") (pin "A") (pintype "passive"))
      (node (ref "R15") (pin "2") (pintype "passive"))
    )
    (net (code "25") (name "Net-(D5-PadA)") (class "Default")
      (node (ref "D5") (pin "A") (pintype "passive"))
      (node (ref "R16") (pin "2") (pintype "passive"))
    )
    (net (code "26") (name "Net-(D6-PadA)") (class "Default")
      (node (ref "D6") (pin "A") (pintype "passive"))
      (node (ref "R17") (pin "2") (pintype "passive"))
    )
    (net (code "27") (name "Net-(D7-PadA)") (class "Default")
      (node (ref "D7") (pin "A") (pintype "passive"))
      (node (ref "R18") (pin "2") (pintype "passive"))
    )
    (net (code "28") (name "Net-(D8-PadK)") (class "Default")
      (node (ref "D8") (pin "K") (pintype "passive"))
      (node (ref "R34") (pin "2") (pintype "passive"))
    )
    (net (code "29") (name "Net-(D9-PadK)") (class "Default")
      (node (ref "D9") (pin "K") (pintype "passive"))
      (node (ref "R35") (pin "2") (pintype "passive"))
    )
    (net (code "30") (name "Net-(J3-VBUS1)") (class "Default")
      (node (ref "F2") (pin "2") (pintype "passive"))
      (node (ref "J3") (pin "A4") (pinfunction "VBUS1_A4") (pintype "passive"))
      (node (ref "J3") (pin "A9") (pinfunction "VBUS2_A9") (pintype "passive"))
      (node (ref "J3") (pin "B4") (pinfunction "VBUS3_B4") (pintype "passive"))
      (node (ref "J3") (pin "B9") (pinfunction "VBUS4_B9") (pintype "passive"))
    )
    (net (code "31") (name "Net-(Q2-PadG)") (class "Default")
      (node (ref "Q2") (pin "G") (pinfunction "G_G") (pintype "passive"))
      (node (ref "R36") (pin "1") (pintype "passive"))
      (node (ref "R6") (pin "2") (pintype "passive"))
    )
    (net (code "32") (name "Net-(Q3-PadD)") (class "Default")
      (node (ref "Q3") (pin "D") (pinfunction "D_D") (pintype "passive"))
      (node (ref "R7") (pin "1") (pintype "passive"))
    )
    (net (code "33") (name "Net-(R24-Pad1)") (class "Default")
      (node (ref "R24") (pin "1") (pintype "passive"))
      (node (ref "R29") (pin "2") (pintype "passive"))
    )
    (net (code "34") (name "Net-(U1-EN)") (class "Default")
      (node (ref "R3") (pin "1") (pintype "passive"))
      (node (ref "R8") (pin "2") (pintype "passive"))
      (node (ref "TP5") (pin "1") (pinfunction "1_1") (pintype "passive"))
      (node (ref "U1") (pin "3") (pinfunction "EN_3") (pintype "input"))
    )
    (net (code "35") (name "Net-(U1-FB)") (class "Default")
      (node (ref "C2") (pin "1") (pintype "passive"))
      (node (ref "R5") (pin "1") (pintype "passive"))
      (node (ref "R9") (pin "1") (pintype "passive"))
      (node (ref "U1") (pin "4") (pinfunction "FB_4") (pintype "input"))
    )
    (net (code "36") (name "Net-(U1-PGATE)") (class "Default")
      (node (ref "Q1") (pin "G") (pinfunction "G_G") (pintype "passive"))
      (node (ref "U1") (pin "7") (pinfunction "PGATE_7") (pintype "output"))
    )
    (net (code "37") (name "Net-(U2-ADDR0)") (class "Default")
      (node (ref "R14") (pin "2") (pintype "passive"))
      (node (ref "U2") (pin "7") (pinfunction "ADDR0_7") (pintype "input"))
    )
    (net (code "38") (name "Net-(U3-OUT1)") (class "Default")
      (node (ref "D4") (pin "K") (pintype "passive"))
      (node (ref "U3") (pin "1") (pinfunction "OUT2_1") (pintype "passive"))
      (node (ref "U3") (pin "2") (pinfunction "OUT1_2") (pintype "passive"))
    )
    (net (code "39") (name "Net-(U3-OUT3)") (class "Default")
      (node (ref "D5") (pin "K") (pintype "passive"))
      (node (ref "U3") (pin "13") (pinfunction "OUT4_13") (pintype "passive"))
      (node (ref "U3") (pin "14") (pinfunction "OUT3_14") (pintype "passive"))
    )
    (net (code "40") (name "Net-(U4-OUT1)") (class "Default")
      (node (ref "D6") (pin "K") (pintype "passive"))
      (node (ref "U4") (pin "1") (pinfunction "OUT2_1") (pintype "passive"))
      (node (ref "U4") (pin "2") (pinfunction "OUT1_2") (pintype "passive"))
    )
    (net (code "41") (name "Net-(U4-OUT3)") (class "Default")
      (node (ref "D7") (pin "K") (pintype "passive"))
      (node (ref "U4") (pin "13") (pinfunction "OUT4_13") (pintype "passive"))
      (node (ref "U4") (pin "14") (pinfunction "OUT3_14") (pintype "passive"))
    )
    (net (code "42") (name "VBUS") (class "Default")
      (node (ref "C9") (pin "2") (pintype "passive"))
      (node (ref "D3") (pin "K") (pinfunction "K_K") (pintype "passive"))
      (node (ref "F2") (pin "1") (pintype "passive"))
      (node (ref "Q2") (pin "D") (pinfunction "D_D") (pintype "passive"))
      (node (ref "TP3") (pin "1") (pinfunction "1_1") (pintype "passive"))
      (node (ref "U2") (pin "10") (pinfunction "VBUS_SENSE_10") (pintype "input"))
    )
    (net (code "43") (name "VIN") (class "Default")
      (node (ref "C1") (pin "2") (pintype "passive"))
      (node (ref "C10") (pin "2") (pintype "passive"))
      (node (ref "C11") (pin "2") (pintype "passive"))
      (node (ref "C12") (pin "2") (pintype "passive"))
      (node (ref "D8") (pin "A") (pintype "passive"))
      (node (ref "F1") (pin "2") (pintype "passive"))
      (node (ref "Q1") (pin "S") (pinfunction "S_S") (pintype "passive"))
      (node (ref "R3") (pin "2") (pintype "passive"))
      (node (ref "R31") (pin "2") (pintype "passive"))
      (node (ref "R4") (pin "2") (pintype "passive"))
      (node (ref "TP1") (pin "1") (pinfunction "1_1") (pintype "passive"))
      (node (ref "U1") (pin "8") (pinfunction "VIN_8") (pintype "power_in"))
    )
    (net (code "44") (name "VSRC") (class "Default")
      (node (ref "C13") (pin "1") (pintype "passive"))
      (node (ref "C2") (pin "2") (pintype "passive"))
      (node (ref "C5") (pin "1") (pintype "passive"))
      (node (ref "C6") (pin "2") (pintype "passive"))
      (node (ref "C7") (pin "1") (pintype "passive"))
      (node (ref "C8") (pin "1") (pintype "passive"))
      (node (ref "D9") (pin "A") (pintype "passive"))
      (node (ref "L1") (pin "2") (pintype "passive"))
      (node (ref "Q2") (pin "S") (pinfunction "S_S") (pintype "passive"))
      (node (ref "Q3") (pin "S") (pinfunction "S_S") (pintype "passive"))
      (node (ref "R1") (pin "2") (pintype "passive"))
      (node (ref "R19") (pin "1") (pintype "passive"))
      (node (ref "R36") (pin "2") (pintype "passive"))
      (node (ref "R5") (pin "2") (pintype "passive"))
      (node (ref "TP2") (pin "1") (pinfunction "1_1") (pintype "passive"))
      (node (ref "U2") (pin "15") (pinfunction "VDD_15") (pintype "power_in"))
      (node (ref "U5") (pin "1") (pinfunction "VIN_1") (pintype "passive"))
    )
    (net (code "45") (name "unconnected-(J3-D1+-PadA6)") (class "Default")
      (node (ref "J3") (pin "A6") (pinfunction "D1+_A6") (pintype "passive"))
    )
    (net (code "46") (name "unconnected-(J3-D1--PadA7)") (class "Default")
      (node (ref "J3") (pin "A7") (pinfunction "D1-_A7") (pintype "passive"))
    )
    (net (code "47") (name "unconnected-(J3-D2+-PadB6)") (class "Default")
      (node (ref "J3") (pin "B6") (pinfunction "D2+_B6") (pintype "passive"))
    )
    (net (code "48") (name "unconnected-(J3-D2--PadB7)") (class "Default")
      (node (ref "J3") (pin "B7") (pinfunction "D2-_B7") (pintype "passive"))
    )
    (net (code "49") (name "unconnected-(J3-RX1+-PadB11)") (class "Default")
      (node (ref "J3") (pin "B11") (pinfunction "RX1+_B11") (pintype "passive+no_connect"))
    )
    (net (code "50") (name "unconnected-(J3-RX1--PadB10)") (class "Default")
      (node (ref "J3") (pin "B10") (pinfunction "RX1-_B10") (pintype "passive+no_connect"))
    )
    (net (code "51") (name "unconnected-(J3-RX2+-PadA11)") (class "Default")
      (node (ref "J3") (pin "A11") (pinfunction "RX2+_A11") (pintype "passive+no_connect"))
    )
    (net (code "52") (name "unconnected-(J3-RX2--PadA10)") (class "Default")
      (node (ref "J3") (pin "A10") (pinfunction "RX2-_A10") (pintype "passive+no_connect"))
    )
    (net (code "53") (name "unconnected-(J3-SBU1-PadA8)") (class "Default")
      (node (ref "J3") (pin "A8") (pinfunction "SBU1_A8") (pintype "passive+no_connect"))
    )
    (net (code "54") (name "unconnected-(J3-SBU2-PadB8)") (class "Default")
      (node (ref "J3") (pin "B8") (pinfunction "SBU2_B8") (pintype "passive+no_connect"))
    )
    (net (code "55") (name "unconnected-(J3-TX1+-PadA2)") (class "Default")
      (node (ref "J3") (pin "A2") (pinfunction "TX1+_A2") (pintype "passive+no_connect"))
    )
    (net (code "56") (name "unconnected-(J3-TX1--PadA3)") (class "Default")
      (node (ref "J3") (pin "A3") (pinfunction "TX1-_A3") (pintype "passive+no_connect"))
    )
    (net (code "57") (name "unconnected-(J3-TX2+-PadB2)") (class "Default")
      (node (ref "J3") (pin "B2") (pinfunction "TX2+_B2") (pintype "passive+no_connect"))
    )
    (net (code "58") (name "unconnected-(J3-TX2--PadB3)") (class "Default")
      (node (ref "J3") (pin "B3") (pinfunction "TX2-_B3") (pintype "passive+no_connect"))
    )
  )
)
